# Fast_Servo.net
KiCad netlist of a schematic drawn in Altium Designer
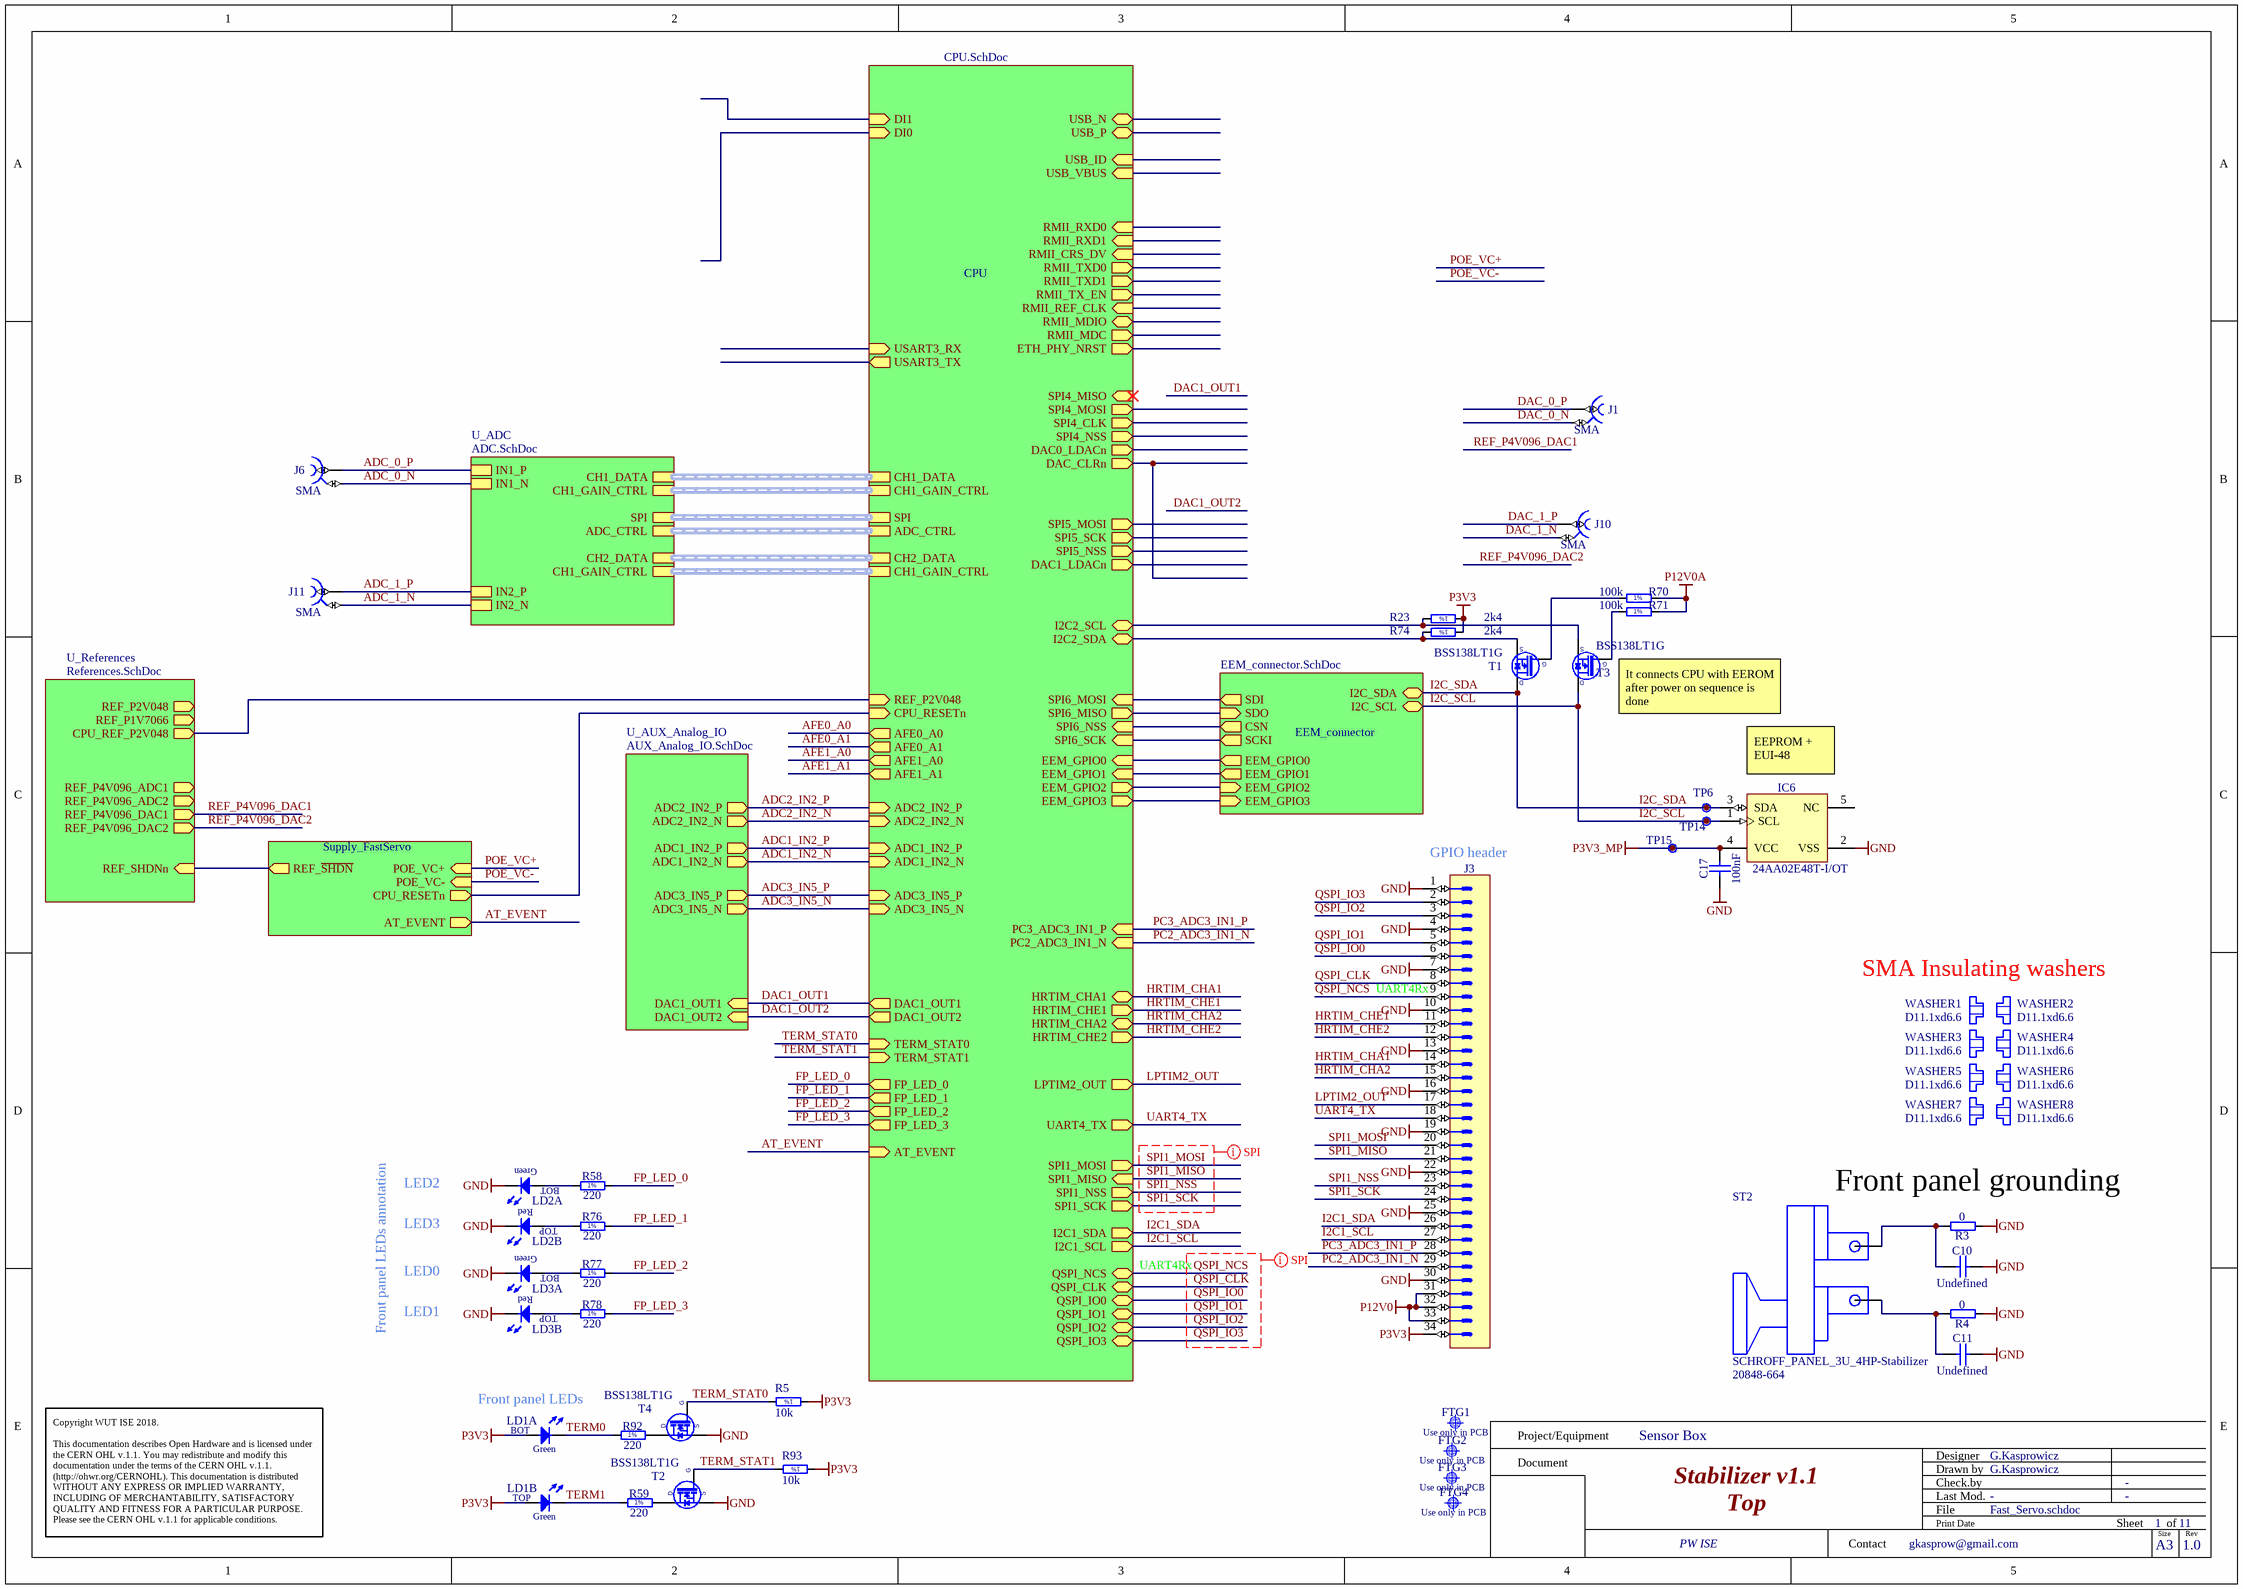
[diagram p0: Fast_Servo.schdoc]

(export (version "E")
  (design (tool "Eeschema 10.0.6"))
  (components
    (comp (ref "C10")
      (value "Undefined")
      (footprint "CAPC2012X135N")
      (description "Non-polarised capacitor")
      (fields (field (name "PART NUMBER") "CC0805_NO-VALUE") (field (name "AUTHOR") "CERN DEM JLC"))
      (libsource (lib "Capacitors") (part "Capacitor - non polarized"))
    )
    (comp (ref "C11")
      (value "Undefined")
      (footprint "CAPC2012X135N")
      (description "Non-polarised capacitor")
      (fields (field (name "PART NUMBER") "CC0805_NO-VALUE") (field (name "AUTHOR") "CERN DEM JLC"))
      (libsource (lib "Capacitors") (part "Capacitor - non polarized"))
    )
    (comp (ref "C17")
      (value "100nF")
      (footprint "CAPC1005X55N")
      (description "Non-polarised capacitor")
      (fields
        (field (name "PART NUMBER") "CC0402_100NF_16V_10%_X5R")
        (field (name "VOLTAGE") "16V")
        (field (name "AUTHOR") "CERN DEM JLC")
      )
      (libsource (lib "Capacitors") (part "Capacitor - non polarized"))
    )
    (comp (ref "FTG1")
      (value "Use only in PCB")
      (footprint "FIDUCIAL_TOP_C100-200")
      (description "Fiducial Target")
      (fields (field (name "PART NUMBER") "FIDUCIAL_TARGET_C100-200") (field (name "AUTHOR") "CERN DEM JLC"))
      (libsource (lib "Eletro-mechanical") (part "Fiducial Target"))
    )
    (comp (ref "FTG2")
      (value "Use only in PCB")
      (footprint "FIDUCIAL_TOP_S100-200")
      (description "Fiducial Target")
      (fields (field (name "PART NUMBER") "FIDUCIAL_TARGET_S100-200") (field (name "AUTHOR") "CERN DEM JLC"))
      (libsource (lib "Eletro-mechanical") (part "Fiducial Target"))
    )
    (comp (ref "FTG3")
      (value "Use only in PCB")
      (footprint "FIDUCIAL_TOP_S100-200")
      (description "Fiducial Target")
      (fields (field (name "PART NUMBER") "FIDUCIAL_TARGET_S100-200") (field (name "AUTHOR") "CERN DEM JLC"))
      (libsource (lib "Eletro-mechanical") (part "Fiducial Target"))
    )
    (comp (ref "FTG4")
      (value "Use only in PCB")
      (footprint "FIDUCIAL_TOP_S100-200")
      (description "Fiducial Target")
      (fields (field (name "PART NUMBER") "FIDUCIAL_TARGET_S100-200") (field (name "AUTHOR") "CERN DEM JLC"))
      (libsource (lib "Eletro-mechanical") (part "Fiducial Target"))
    )
    (comp (ref "IC6")
      (value "24AA02E48T-I/OT")
      (footprint "SOT95P280X145-5N")
      (description "1.7V-5.5V, 2K I2C Serial EEPROM With EUI-48 Node Identity")
      (fields (field (name "MANUFACTURER") "MICROCHIP TECHNOLOGY") (field (name "AUTHOR") "CERN DEM MR"))
      (libsource (lib "ICs And Semiconductors") (part "24AA02E48T-I/OT"))
    )
    (comp (ref "J1")
      (value "SMA")
      (footprint "RF249BT0050GHDW")
      (description "50 Ohm Through Hole SMA Right Angle PCB Jack")
      (fields
        (field (name "PART NUMBER") "AdamTech_RF249BT0050GHDW")
        (field (name "MANUFACTURER") "AdamTech")
        (field (name "AUTHOR") "GK")
      )
      (libsource (lib "") (part "CON_SMA_RF249BT0050GHDW_1"))
    )
    (comp (ref "J3")
      (value "Header 34")
      (footprint "3M_N2534-6002RB")
      (description "Connector 34 Male")
      (fields
        (field (name "PART NUMBER") "3M_N2534-6002RB")
        (field (name "MANUFACTURER") "3M")
        (field (name "AUTHOR") "CERN DEM JLC")
      )
      (libsource (lib "Connectors") (part "Connector 34 Male"))
    )
    (comp (ref "J6")
      (value "SMA")
      (footprint "RF249BT0050GHDW")
      (description "50 Ohm Through Hole SMA Right Angle PCB Jack")
      (fields
        (field (name "PART NUMBER") "AdamTech_RF249BT0050GHDW")
        (field (name "MANUFACTURER") "AdamTech")
        (field (name "AUTHOR") "GK")
      )
      (libsource (lib "LIBRARY_SCH") (part "CON_SMA_RF249BT0050GHDW"))
    )
    (comp (ref "J10")
      (value "SMA")
      (footprint "RF249BT0050GHDW")
      (description "50 Ohm Through Hole SMA Right Angle PCB Jack")
      (fields
        (field (name "PART NUMBER") "AdamTech_RF249BT0050GHDW")
        (field (name "MANUFACTURER") "AdamTech")
        (field (name "AUTHOR") "GK")
      )
      (libsource (lib "") (part "CON_SMA_RF249BT0050GHDW_1"))
    )
    (comp (ref "J11")
      (value "SMA")
      (footprint "RF249BT0050GHDW")
      (description "50 Ohm Through Hole SMA Right Angle PCB Jack")
      (fields
        (field (name "PART NUMBER") "AdamTech_RF249BT0050GHDW")
        (field (name "MANUFACTURER") "AdamTech")
        (field (name "AUTHOR") "GK")
      )
      (libsource (lib "LIBRARY_SCH") (part "CON_SMA_RF249BT0050GHDW"))
    )
    (comp (ref "LD1")
      (value "Green/Green")
      (footprint "LED_DIALIGHT_571-0122F")
      (description "LED x2 Green 1C2A-BOT_3C4A-TOP")
      (fields
        (field (name "PART NUMBER") "LED_DIALIGHT_571-0122F")
        (field (name "MANUFACTURER") "DIALIGHT")
        (field (name "AUTHOR") "CERN DEM JLC")
      )
      (libsource (lib "ICs And Semiconductors") (part "LED x2 Green 1C2A-BOT_3C4A-TOP"))
    )
    (comp (ref "LD2")
      (value "Red/Green")
      (footprint "LED_DIALIGHT_571-0112F")
      (description "2x LED  Botom Green, Top Red")
      (fields
        (field (name "PART NUMBER") "LED_DIALIGHT_571-0112F")
        (field (name "MANUFACTURER") "DIALIGHT")
        (field (name "AUTHOR") "CERN DEM JLC")
      )
      (libsource (lib "ICs And Semiconductors") (part "LED x2 G-1C2A-BOT_R-3C4A-TOP"))
    )
    (comp (ref "LD3")
      (value "Red/Green")
      (footprint "LED_DIALIGHT_571-0112F")
      (description "2x LED  Botom Green, Top Red")
      (fields
        (field (name "PART NUMBER") "LED_DIALIGHT_571-0112F")
        (field (name "MANUFACTURER") "DIALIGHT")
        (field (name "AUTHOR") "CERN DEM JLC")
      )
      (libsource (lib "ICs And Semiconductors") (part "LED x2 G-1C2A-BOT_R-3C4A-TOP"))
    )
    (comp (ref "R3")
      (value "0")
      (footprint "RESC1608X55N")
      (description "Resistor")
      (fields
        (field (name "PART NUMBER") "R0603_0R_JUMPER")
        (field (name "MANUFACTURER") "GENERIC")
        (field (name "AUTHOR") "CERN DEM JLC")
      )
      (libsource (lib "Resistors") (part "Resistor"))
    )
    (comp (ref "R4")
      (value "0")
      (footprint "RESC1608X55N")
      (description "Resistor")
      (fields
        (field (name "PART NUMBER") "R0603_0R_JUMPER")
        (field (name "MANUFACTURER") "GENERIC")
        (field (name "AUTHOR") "CERN DEM JLC")
      )
      (libsource (lib "Resistors") (part "Resistor"))
    )
    (comp (ref "R5")
      (value "10k")
      (footprint "RESC1005X40N")
      (description "Resistor - 1%")
      (fields
        (field (name "PART NUMBER") "R0402_10K_1%_0.0625W_100PPM")
        (field (name "POWER") "0.0625W")
        (field (name "AUTHOR") "CERN DEM JLC")
      )
      (libsource (lib "Resistors") (part "Resistor - 1%"))
    )
    (comp (ref "R23")
      (value "2k4")
      (footprint "RESC1005X40N")
      (description "Resistor - 1%")
      (fields
        (field (name "PART NUMBER") "R0402_2K4_1%_0.0625W_100PPM")
        (field (name "POWER") "0.0625W")
        (field (name "AUTHOR") "CERN DEM JLC")
      )
      (libsource (lib "Resistors") (part "Resistor - 1%"))
    )
    (comp (ref "R58")
      (value "220")
      (footprint "RESC1608X55N")
      (description "Resistor - 1%")
      (fields
        (field (name "PART NUMBER") "R0603_220R_1%_0.1W_100PPM")
        (field (name "POWER") "0.1W")
        (field (name "AUTHOR") "CERN DEM JLC")
      )
      (libsource (lib "Resistors") (part "Resistor - 1%"))
    )
    (comp (ref "R59")
      (value "220")
      (footprint "RESC1608X55N")
      (description "Resistor - 1%")
      (fields
        (field (name "PART NUMBER") "R0603_220R_1%_0.1W_100PPM")
        (field (name "POWER") "0.1W")
        (field (name "AUTHOR") "CERN DEM JLC")
      )
      (libsource (lib "Resistors") (part "Resistor - 1%"))
    )
    (comp (ref "R70")
      (value "100k")
      (footprint "RESC1005X40N")
      (description "Resistor - 1%")
      (fields
        (field (name "PART NUMBER") "R0402_100K_1%_0.0625W_100PPM")
        (field (name "POWER") "0.0625W")
        (field (name "AUTHOR") "CERN DEM JLC")
      )
      (libsource (lib "Resistors") (part "Resistor - 1%"))
    )
    (comp (ref "R71")
      (value "100k")
      (footprint "RESC1005X40N")
      (description "Resistor - 1%")
      (fields
        (field (name "PART NUMBER") "R0402_100K_1%_0.0625W_100PPM")
        (field (name "POWER") "0.0625W")
        (field (name "AUTHOR") "CERN DEM JLC")
      )
      (libsource (lib "Resistors") (part "Resistor - 1%"))
    )
    (comp (ref "R74")
      (value "2k4")
      (footprint "RESC1005X40N")
      (description "Resistor - 1%")
      (fields
        (field (name "PART NUMBER") "R0402_2K4_1%_0.0625W_100PPM")
        (field (name "POWER") "0.0625W")
        (field (name "AUTHOR") "CERN DEM JLC")
      )
      (libsource (lib "Resistors") (part "Resistor - 1%"))
    )
    (comp (ref "R76")
      (value "220")
      (footprint "RESC1608X55N")
      (description "Resistor - 1%")
      (fields
        (field (name "PART NUMBER") "R0603_220R_1%_0.1W_100PPM")
        (field (name "POWER") "0.1W")
        (field (name "AUTHOR") "CERN DEM JLC")
      )
      (libsource (lib "Resistors") (part "Resistor - 1%"))
    )
    (comp (ref "R77")
      (value "220")
      (footprint "RESC1608X55N")
      (description "Resistor - 1%")
      (fields
        (field (name "PART NUMBER") "R0603_220R_1%_0.1W_100PPM")
        (field (name "POWER") "0.1W")
        (field (name "AUTHOR") "CERN DEM JLC")
      )
      (libsource (lib "Resistors") (part "Resistor - 1%"))
    )
    (comp (ref "R78")
      (value "220")
      (footprint "RESC1608X55N")
      (description "Resistor - 1%")
      (fields
        (field (name "PART NUMBER") "R0603_220R_1%_0.1W_100PPM")
        (field (name "POWER") "0.1W")
        (field (name "AUTHOR") "CERN DEM JLC")
      )
      (libsource (lib "Resistors") (part "Resistor - 1%"))
    )
    (comp (ref "R92")
      (value "220")
      (footprint "RESC1608X55N")
      (description "Resistor - 1%")
      (fields
        (field (name "PART NUMBER") "R0603_220R_1%_0.1W_100PPM")
        (field (name "POWER") "0.1W")
        (field (name "AUTHOR") "CERN DEM JLC")
      )
      (libsource (lib "Resistors") (part "Resistor - 1%"))
    )
    (comp (ref "R93")
      (value "10k")
      (footprint "RESC1005X40N")
      (description "Resistor - 1%")
      (fields
        (field (name "PART NUMBER") "R0402_10K_1%_0.0625W_100PPM")
        (field (name "POWER") "0.0625W")
        (field (name "AUTHOR") "CERN DEM JLC")
      )
      (libsource (lib "Resistors") (part "Resistor - 1%"))
    )
    (comp (ref "ST2")
      (value "SCHROFF_PANEL_3U_4HP-Stabilizer")
      (footprint "SCHROFF_PANEL_3HP_4U - Stabilizer")
      (description "Schroff 3HP 4U EUROCARD Panel")
      (fields
        (field (name "MANUFACTURER") "Schroff")
        (field (name "MANUFACTURER PART NUMBER") "20818-017")
        (field (name "MANUFACTURER PART NUMBER 2") "20848-664")
      )
      (libsource (lib "Mechanical") (part "SCHROFF_PANEL_3U_4HP_Stabilizer"))
    )
    (comp (ref "T1")
      (value "BSS138LT1G")
      (footprint "SOT95P240X110-3N")
      (description "N-CHANNEL MOSFET WITH DIODE")
      (fields (field (name "MANUFACTURER") "ON SEMICONDUCTOR") (field (name "AUTHOR") "CERN DEM JLC"))
      (libsource (lib "ICs And Semiconductors") (part "N-MOSFET-D 1G 2S 3D"))
    )
    (comp (ref "T2")
      (value "BSS138LT1G")
      (footprint "SOT95P240X110-3N")
      (description "N-CHANNEL MOSFET WITH DIODE")
      (fields (field (name "MANUFACTURER") "ON SEMICONDUCTOR") (field (name "AUTHOR") "CERN DEM JLC"))
      (libsource (lib "ICs And Semiconductors") (part "N-MOSFET-D 1G 2S 3D"))
    )
    (comp (ref "T3")
      (value "BSS138LT1G")
      (footprint "SOT95P240X110-3N")
      (description "N-CHANNEL MOSFET WITH DIODE")
      (fields (field (name "MANUFACTURER") "ON SEMICONDUCTOR") (field (name "AUTHOR") "CERN DEM JLC"))
      (libsource (lib "ICs And Semiconductors") (part "N-MOSFET-D 1G 2S 3D"))
    )
    (comp (ref "T4")
      (value "BSS138LT1G")
      (footprint "SOT95P240X110-3N")
      (description "N-CHANNEL MOSFET WITH DIODE")
      (fields (field (name "MANUFACTURER") "ON SEMICONDUCTOR") (field (name "AUTHOR") "CERN DEM JLC"))
      (libsource (lib "ICs And Semiconductors") (part "N-MOSFET-D 1G 2S 3D"))
    )
    (comp (ref "TP6")
      (value "Test Point")
      (footprint "TPS127")
      (fields (field (name "PART NUMBER") "SMD_PAD_1.27X1.27MM") (field (name "AUTHOR") "CERN DEM JLC"))
      (libsource (lib "Eletro-mechanical") (part "Test Point"))
    )
    (comp (ref "TP14")
      (value "Test Point")
      (footprint "TPS127")
      (fields (field (name "PART NUMBER") "SMD_PAD_1.27X1.27MM") (field (name "AUTHOR") "CERN DEM JLC"))
      (libsource (lib "Eletro-mechanical") (part "Test Point"))
    )
    (comp (ref "TP15")
      (value "Test Point")
      (footprint "TPS127")
      (fields (field (name "PART NUMBER") "SMD_PAD_1.27X1.27MM") (field (name "AUTHOR") "CERN DEM JLC"))
      (libsource (lib "Eletro-mechanical") (part "Test Point"))
    )
    (comp (ref "WASHER1")
      (value "D11.1xd6.6")
      (footprint "Keystone_7687")
      (description "SMA_Shoulder Washer")
      (fields
        (field (name "PART NUMBER") "Keystone 7687")
        (field (name "MANUFACTURER") "Keystone")
        (field (name "AUTHOR") "GK")
      )
      (libsource (lib "LIBRARY_SCH") (part "Keystone_7687"))
    )
    (comp (ref "WASHER2")
      (value "D11.1xd6.6")
      (footprint "Keystone_7687")
      (description "SMA_Shoulder Washer")
      (fields
        (field (name "PART NUMBER") "Keystone 7687")
        (field (name "MANUFACTURER") "Keystone")
        (field (name "AUTHOR") "GK")
      )
      (libsource (lib "LIBRARY_SCH") (part "Keystone_7687"))
    )
    (comp (ref "WASHER3")
      (value "D11.1xd6.6")
      (footprint "Keystone_7687")
      (description "SMA_Shoulder Washer")
      (fields
        (field (name "PART NUMBER") "Keystone 7687")
        (field (name "MANUFACTURER") "Keystone")
        (field (name "AUTHOR") "GK")
      )
      (libsource (lib "LIBRARY_SCH") (part "Keystone_7687"))
    )
    (comp (ref "WASHER4")
      (value "D11.1xd6.6")
      (footprint "Keystone_7687")
      (description "SMA_Shoulder Washer")
      (fields
        (field (name "PART NUMBER") "Keystone 7687")
        (field (name "MANUFACTURER") "Keystone")
        (field (name "AUTHOR") "GK")
      )
      (libsource (lib "LIBRARY_SCH") (part "Keystone_7687"))
    )
    (comp (ref "WASHER5")
      (value "D11.1xd6.6")
      (footprint "Keystone_7687")
      (description "SMA_Shoulder Washer")
      (fields
        (field (name "PART NUMBER") "Keystone 7687")
        (field (name "MANUFACTURER") "Keystone")
        (field (name "AUTHOR") "GK")
      )
      (libsource (lib "LIBRARY_SCH") (part "Keystone_7687"))
    )
    (comp (ref "WASHER6")
      (value "D11.1xd6.6")
      (footprint "Keystone_7687")
      (description "SMA_Shoulder Washer")
      (fields
        (field (name "PART NUMBER") "Keystone 7687")
        (field (name "MANUFACTURER") "Keystone")
        (field (name "AUTHOR") "GK")
      )
      (libsource (lib "LIBRARY_SCH") (part "Keystone_7687"))
    )
    (comp (ref "WASHER7")
      (value "D11.1xd6.6")
      (footprint "Keystone_7687")
      (description "SMA_Shoulder Washer")
      (fields
        (field (name "PART NUMBER") "Keystone 7687")
        (field (name "MANUFACTURER") "Keystone")
        (field (name "AUTHOR") "GK")
      )
      (libsource (lib "LIBRARY_SCH") (part "Keystone_7687"))
    )
    (comp (ref "WASHER8")
      (value "D11.1xd6.6")
      (footprint "Keystone_7687")
      (description "SMA_Shoulder Washer")
      (fields
        (field (name "PART NUMBER") "Keystone 7687")
        (field (name "MANUFACTURER") "Keystone")
        (field (name "AUTHOR") "GK")
      )
      (libsource (lib "LIBRARY_SCH") (part "Keystone_7687"))
    )
  )
  (nets
    (net (code "7") (name "/ADC_0_N") (class "Default")
      (node (ref "J6") (pin "2") (pinfunction "2_2") (pintype "bidirectional"))
    )
    (net (code "8") (name "/ADC_0_P") (class "Default")
      (node (ref "J6") (pin "1") (pinfunction "1_1") (pintype "bidirectional"))
    )
    (net (code "9") (name "/ADC_1_N") (class "Default")
      (node (ref "J11") (pin "2") (pinfunction "2_2") (pintype "bidirectional"))
    )
    (net (code "10") (name "/ADC_1_P") (class "Default")
      (node (ref "J11") (pin "1") (pinfunction "1_1") (pintype "bidirectional"))
    )
    (net (code "28") (name "/DAC_0_N") (class "Default")
      (node (ref "J1") (pin "2") (pinfunction "2_2") (pintype "bidirectional"))
    )
    (net (code "29") (name "/DAC_0_P") (class "Default")
      (node (ref "J1") (pin "1") (pinfunction "1_1") (pintype "bidirectional"))
    )
    (net (code "30") (name "/DAC_1_N") (class "Default")
      (node (ref "J10") (pin "2") (pinfunction "2_2") (pintype "bidirectional"))
    )
    (net (code "31") (name "/DAC_1_P") (class "Default")
      (node (ref "J10") (pin "1") (pinfunction "1_1") (pintype "bidirectional"))
    )
    (net (code "40") (name "/FP_LED_0") (class "Default")
      (node (ref "R58") (pin "2") (pinfunction "2_2") (pintype "passive"))
    )
    (net (code "41") (name "/FP_LED_1") (class "Default")
      (node (ref "R76") (pin "2") (pinfunction "2_2") (pintype "passive"))
    )
    (net (code "42") (name "/FP_LED_2") (class "Default")
      (node (ref "R77") (pin "2") (pinfunction "2_2") (pintype "passive"))
    )
    (net (code "43") (name "/FP_LED_3") (class "Default")
      (node (ref "R78") (pin "2") (pinfunction "2_2") (pintype "passive"))
    )
    (net (code "44") (name "/HRTIM_CHA1") (class "Default")
      (node (ref "J3") (pin "14") (pinfunction "14_14") (pintype "bidirectional"))
    )
    (net (code "45") (name "/HRTIM_CHA2") (class "Default")
      (node (ref "J3") (pin "15") (pinfunction "15_15") (pintype "bidirectional"))
    )
    (net (code "46") (name "/HRTIM_CHE1") (class "Default")
      (node (ref "J3") (pin "11") (pinfunction "11_11") (pintype "bidirectional"))
    )
    (net (code "47") (name "/HRTIM_CHE2") (class "Default")
      (node (ref "J3") (pin "12") (pinfunction "12_12") (pintype "bidirectional"))
    )
    (net (code "48") (name "/I2C1_SCL") (class "Default")
      (node (ref "J3") (pin "27") (pinfunction "27_27") (pintype "bidirectional"))
    )
    (net (code "49") (name "/I2C1_SDA") (class "Default")
      (node (ref "J3") (pin "26") (pinfunction "26_26") (pintype "bidirectional"))
    )
    (net (code "50") (name "/I2C2_SCL") (class "Default")
      (node (ref "R23") (pin "2") (pinfunction "2_2") (pintype "passive"))
      (node (ref "T3") (pin "2") (pinfunction "S_2") (pintype "passive"))
    )
    (net (code "51") (name "/I2C2_SDA") (class "Default")
      (node (ref "R74") (pin "2") (pinfunction "2_2") (pintype "passive"))
      (node (ref "T1") (pin "2") (pinfunction "S_2") (pintype "passive"))
    )
    (net (code "52") (name "/I2C_SCL") (class "Default")
      (node (ref "IC6") (pin "1") (pinfunction "SCL_1") (pintype "input"))
      (node (ref "T3") (pin "3") (pinfunction "D_3") (pintype "passive"))
      (node (ref "TP14") (pin "1") (pinfunction "1_1") (pintype "bidirectional"))
    )
    (net (code "53") (name "/I2C_SDA") (class "Default")
      (node (ref "IC6") (pin "3") (pinfunction "SDA_3") (pintype "bidirectional"))
      (node (ref "T1") (pin "3") (pinfunction "D_3") (pintype "passive"))
      (node (ref "TP6") (pin "1") (pinfunction "1_1") (pintype "bidirectional"))
    )
    (net (code "54") (name "/LPTIM2_OUT") (class "Default")
      (node (ref "J3") (pin "17") (pinfunction "17_17") (pintype "bidirectional"))
    )
    (net (code "55") (name "/PC2_ADC3_IN1_N") (class "Default")
      (node (ref "J3") (pin "29") (pinfunction "29_29") (pintype "bidirectional"))
    )
    (net (code "56") (name "/PC3_ADC3_IN1_P") (class "Default")
      (node (ref "J3") (pin "28") (pinfunction "28_28") (pintype "bidirectional"))
    )
    (net (code "59") (name "/QSPI_CLK") (class "Default")
      (node (ref "J3") (pin "8") (pinfunction "8_8") (pintype "bidirectional"))
    )
    (net (code "60") (name "/QSPI_IO0") (class "Default")
      (node (ref "J3") (pin "6") (pinfunction "6_6") (pintype "bidirectional"))
    )
    (net (code "61") (name "/QSPI_IO1") (class "Default")
      (node (ref "J3") (pin "5") (pinfunction "5_5") (pintype "bidirectional"))
    )
    (net (code "62") (name "/QSPI_IO2") (class "Default")
      (node (ref "J3") (pin "3") (pinfunction "3_3") (pintype "bidirectional"))
    )
    (net (code "63") (name "/QSPI_IO3") (class "Default")
      (node (ref "J3") (pin "2") (pinfunction "2_2") (pintype "bidirectional"))
    )
    (net (code "64") (name "/QSPI_NCS") (class "Default")
      (node (ref "J3") (pin "9") (pinfunction "9_9") (pintype "bidirectional"))
    )
    (net (code "83") (name "/SPI1_MISO") (class "Default")
      (node (ref "J3") (pin "21") (pinfunction "21_21") (pintype "bidirectional"))
    )
    (net (code "84") (name "/SPI1_MOSI") (class "Default")
      (node (ref "J3") (pin "20") (pinfunction "20_20") (pintype "bidirectional"))
    )
    (net (code "85") (name "/SPI1_NSS") (class "Default")
      (node (ref "J3") (pin "23") (pinfunction "23_23") (pintype "bidirectional"))
    )
    (net (code "86") (name "/SPI1_SCK") (class "Default")
      (node (ref "J3") (pin "24") (pinfunction "24_24") (pintype "bidirectional"))
    )
    (net (code "96") (name "/TERM0") (class "Default")
      (node (ref "LD1") (pin "1") (pinfunction "C_1") (pintype "passive"))
      (node (ref "R92") (pin "1") (pinfunction "1_1") (pintype "passive"))
    )
    (net (code "97") (name "/TERM1") (class "Default")
      (node (ref "LD1") (pin "3") (pinfunction "C_3") (pintype "passive"))
      (node (ref "R59") (pin "1") (pinfunction "1_1") (pintype "passive"))
    )
    (net (code "98") (name "/TERM_STAT0") (class "Default")
      (node (ref "R5") (pin "2") (pinfunction "2_2") (pintype "passive"))
      (node (ref "T4") (pin "1") (pinfunction "G_1") (pintype "passive"))
    )
    (net (code "99") (name "/TERM_STAT1") (class "Default")
      (node (ref "R93") (pin "2") (pinfunction "2_2") (pintype "passive"))
      (node (ref "T2") (pin "1") (pinfunction "G_1") (pintype "passive"))
    )
    (net (code "100") (name "/UART4_TX") (class "Default")
      (node (ref "J3") (pin "18") (pinfunction "18_18") (pintype "bidirectional"))
    )
    (net (code "107") (name "GND") (class "Default")
      (node (ref "C10") (pin "2") (pinfunction "2_2") (pintype "passive"))
      (node (ref "C11") (pin "2") (pinfunction "2_2") (pintype "passive"))
      (node (ref "C17") (pin "1") (pinfunction "1_1") (pintype "passive"))
      (node (ref "IC6") (pin "2") (pinfunction "VSS_2") (pintype "power_in"))
      (node (ref "J3") (pin "1") (pinfunction "1_1") (pintype "bidirectional"))
      (node (ref "J3") (pin "10") (pinfunction "10_10") (pintype "bidirectional"))
      (node (ref "J3") (pin "13") (pinfunction "13_13") (pintype "bidirectional"))
      (node (ref "J3") (pin "16") (pinfunction "16_16") (pintype "bidirectional"))
      (node (ref "J3") (pin "19") (pinfunction "19_19") (pintype "bidirectional"))
      (node (ref "J3") (pin "22") (pinfunction "22_22") (pintype "bidirectional"))
      (node (ref "J3") (pin "25") (pinfunction "25_25") (pintype "bidirectional"))
      (node (ref "J3") (pin "30") (pinfunction "30_30") (pintype "bidirectional"))
      (node (ref "J3") (pin "4") (pinfunction "4_4") (pintype "bidirectional"))
      (node (ref "J3") (pin "7") (pinfunction "7_7") (pintype "bidirectional"))
      (node (ref "LD2") (pin "1") (pinfunction "C_1") (pintype "passive"))
      (node (ref "LD2") (pin "3") (pinfunction "C_3") (pintype "passive"))
      (node (ref "LD3") (pin "1") (pinfunction "C_1") (pintype "passive"))
      (node (ref "LD3") (pin "3") (pinfunction "C_3") (pintype "passive"))
      (node (ref "R3") (pin "1") (pinfunction "1_1") (pintype "passive"))
      (node (ref "R4") (pin "1") (pinfunction "1_1") (pintype "passive"))
      (node (ref "T2") (pin "2") (pinfunction "S_2") (pintype "passive"))
      (node (ref "T4") (pin "2") (pinfunction "S_2") (pintype "passive"))
    )
    (net (code "108") (name "Net-(C10-Pad1)") (class "Default")
      (node (ref "C10") (pin "1") (pinfunction "1_1") (pintype "passive"))
      (node (ref "R3") (pin "2") (pinfunction "2_2") (pintype "passive"))
      (node (ref "ST2") (pin "1") (pinfunction "1_1") (pintype "passive"))
    )
    (net (code "109") (name "Net-(C11-Pad1)") (class "Default")
      (node (ref "C11") (pin "1") (pinfunction "1_1") (pintype "passive"))
      (node (ref "R4") (pin "2") (pinfunction "2_2") (pintype "passive"))
      (node (ref "ST2") (pin "0") (pinfunction "0_0") (pintype "passive"))
    )
    (net (code "110") (name "Net-(LD2A-A)") (class "Default")
      (node (ref "LD2") (pin "2") (pinfunction "A_2") (pintype "passive"))
      (node (ref "R58") (pin "1") (pinfunction "1_1") (pintype "passive"))
    )
    (net (code "111") (name "Net-(LD2B-A)") (class "Default")
      (node (ref "LD2") (pin "4") (pinfunction "A_4") (pintype "passive"))
      (node (ref "R76") (pin "1") (pinfunction "1_1") (pintype "passive"))
    )
    (net (code "112") (name "Net-(LD3A-A)") (class "Default")
      (node (ref "LD3") (pin "2") (pinfunction "A_2") (pintype "passive"))
      (node (ref "R77") (pin "1") (pinfunction "1_1") (pintype "passive"))
    )
    (net (code "113") (name "Net-(LD3B-A)") (class "Default")
      (node (ref "LD3") (pin "4") (pinfunction "A_4") (pintype "passive"))
      (node (ref "R78") (pin "1") (pinfunction "1_1") (pintype "passive"))
    )
    (net (code "114") (name "Net-(T1-G)") (class "Default")
      (node (ref "R70") (pin "1") (pinfunction "1_1") (pintype "passive"))
      (node (ref "T1") (pin "1") (pinfunction "G_1") (pintype "passive"))
    )
    (net (code "115") (name "Net-(T2-D)") (class "Default")
      (node (ref "R59") (pin "2") (pinfunction "2_2") (pintype "passive"))
      (node (ref "T2") (pin "3") (pinfunction "D_3") (pintype "passive"))
    )
    (net (code "116") (name "Net-(T3-G)") (class "Default")
      (node (ref "R71") (pin "1") (pinfunction "1_1") (pintype "passive"))
      (node (ref "T3") (pin "1") (pinfunction "G_1") (pintype "passive"))
    )
    (net (code "117") (name "Net-(T4-D)") (class "Default")
      (node (ref "R92") (pin "2") (pinfunction "2_2") (pintype "passive"))
      (node (ref "T4") (pin "3") (pinfunction "D_3") (pintype "passive"))
    )
    (net (code "118") (name "P3V3") (class "Default")
      (node (ref "J3") (pin "34") (pinfunction "34_34") (pintype "bidirectional"))
      (node (ref "LD1") (pin "2") (pinfunction "A_2") (pintype "passive"))
      (node (ref "LD1") (pin "4") (pinfunction "A_4") (pintype "passive"))
      (node (ref "R23") (pin "1") (pinfunction "1_1") (pintype "passive"))
      (node (ref "R5") (pin "1") (pinfunction "1_1") (pintype "passive"))
      (node (ref "R74") (pin "1") (pinfunction "1_1") (pintype "passive"))
      (node (ref "R93") (pin "1") (pinfunction "1_1") (pintype "passive"))
    )
    (net (code "119") (name "P3V3_MP") (class "Default")
      (node (ref "C17") (pin "2") (pinfunction "2_2") (pintype "passive"))
      (node (ref "IC6") (pin "4") (pinfunction "VCC_4") (pintype "power_in"))
      (node (ref "TP15") (pin "1") (pinfunction "1_1") (pintype "bidirectional"))
    )
    (net (code "120") (name "P12V0") (class "Default")
      (node (ref "J3") (pin "31") (pinfunction "31_31") (pintype "bidirectional"))
      (node (ref "J3") (pin "32") (pinfunction "32_32") (pintype "bidirectional"))
      (node (ref "J3") (pin "33") (pinfunction "33_33") (pintype "bidirectional"))
    )
    (net (code "121") (name "P12V0A") (class "Default")
      (node (ref "R70") (pin "2") (pinfunction "2_2") (pintype "passive"))
      (node (ref "R71") (pin "2") (pinfunction "2_2") (pintype "passive"))
    )
    (net (code "122") (name "unconnected-(IC6-NC-Pad5)") (class "Default")
      (node (ref "IC6") (pin "5") (pinfunction "NC_5") (pintype "passive"))
    )
  )
)
